# bmsMaster_isospi.net
KiCad netlist of a schematic drawn in Altium Designer
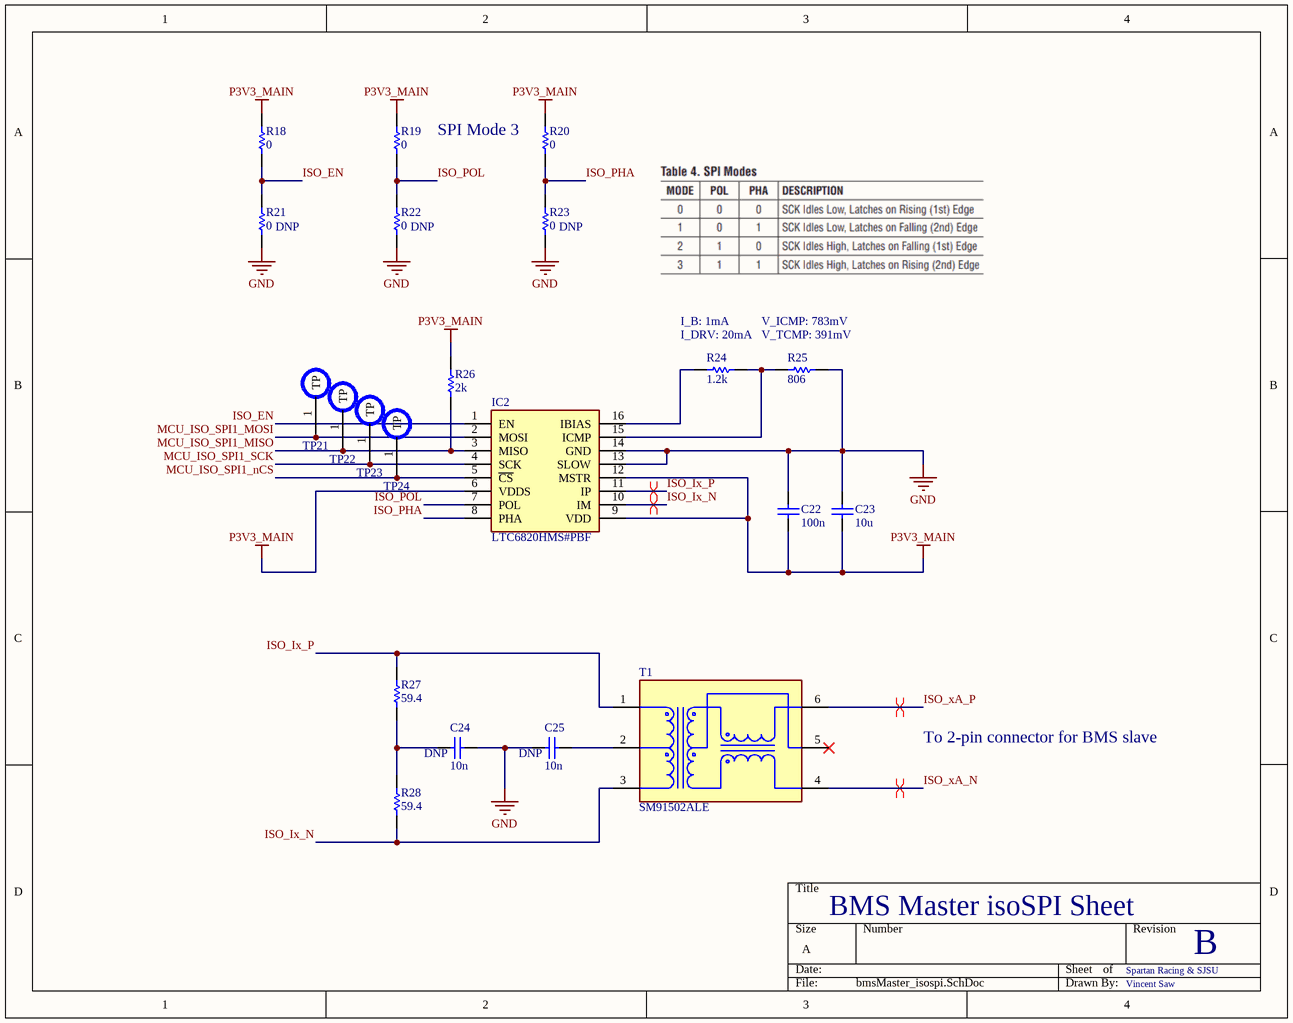
[diagram p0: bmsMaster_isospi.SchDoc]

(export (version "E")
  (design (tool "Eeschema 10.0.6"))
  (components
    (comp (ref "C22")
      (value "100n")
      (footprint "CAPC1608X90N")
      (description "Capacitor")
      (libsource (lib "Simulation Generic Components") (part "Capacitor"))
    )
    (comp (ref "C23")
      (value "10u")
      (footprint "CAPC1608X90N")
      (description "Capacitor")
      (libsource (lib "Simulation Generic Components") (part "Capacitor"))
    )
    (comp (ref "C24")
      (value "10n")
      (footprint "CAPC1608X90N")
      (description "Capacitor")
      (libsource (lib "Simulation Generic Components") (part "Capacitor"))
    )
    (comp (ref "C25")
      (value "10n")
      (footprint "CAPC1608X90N")
      (description "Capacitor")
      (libsource (lib "Simulation Generic Components") (part "Capacitor"))
    )
    (comp (ref "IC2")
      (value "LTC6820HMS#PBF")
      (footprint "SamacSys:SOP50P490X110-16N")
      (description "Integrated Circuit")
      (fields (field (name "MOUSER PART NUMBER") "584-LTC6820HMS#PBF"))
      (libsource (lib "*") (part "LTC6820HMS#PBF"))
    )
    (comp (ref "R18")
      (value "0")
      (footprint "RESC1608X50N")
      (description "Resistor")
      (libsource (lib "Simulation Generic Components") (part "Resistor"))
    )
    (comp (ref "R19")
      (value "0")
      (footprint "RESC1608X50N")
      (description "Resistor")
      (libsource (lib "Simulation Generic Components") (part "Resistor"))
    )
    (comp (ref "R20")
      (value "0")
      (footprint "RESC1608X50N")
      (description "Resistor")
      (libsource (lib "Simulation Generic Components") (part "Resistor"))
    )
    (comp (ref "R21")
      (value "0")
      (footprint "RESC1608X50N")
      (description "Resistor")
      (libsource (lib "Simulation Generic Components") (part "Resistor"))
    )
    (comp (ref "R22")
      (value "0")
      (footprint "RESC1608X50N")
      (description "Resistor")
      (libsource (lib "Simulation Generic Components") (part "Resistor"))
    )
    (comp (ref "R23")
      (value "0")
      (footprint "RESC1608X50N")
      (description "Resistor")
      (libsource (lib "Simulation Generic Components") (part "Resistor"))
    )
    (comp (ref "R24")
      (value "1.2k")
      (footprint "RESC1608X50N")
      (description "Resistor")
      (libsource (lib "Simulation Generic Components") (part "Resistor"))
    )
    (comp (ref "R25")
      (value "806")
      (footprint "RESC1608X50N")
      (description "Resistor")
      (libsource (lib "Simulation Generic Components") (part "Resistor"))
    )
    (comp (ref "R26")
      (value "2k")
      (footprint "RESC1608X50N")
      (description "Resistor")
      (libsource (lib "Simulation Generic Components") (part "Resistor"))
    )
    (comp (ref "R27")
      (value "59.4")
      (footprint "RESC1608X50N")
      (description "Resistor")
      (libsource (lib "Simulation Generic Components") (part "Resistor"))
    )
    (comp (ref "R28")
      (value "59.4")
      (footprint "RESC1608X50N")
      (description "Resistor")
      (libsource (lib "Simulation Generic Components") (part "Resistor"))
    )
    (comp (ref "T1")
      (value "SM91502ALE")
      (footprint "FP-SM91502ALE-MFG")
      (description "BMS XFORMER 1-CH 1000V AECQ +125")
      (fields
        (field (name "MANUFACTURER") "Bourns")
        (field (name "OCTOPART") "https://octopart.com/sm91502ale-bourns-95732123")
      )
      (libsource (lib "Altium Content Vault") (part "554ff5199021d68917f526d8699f58a"))
    )
    (comp (ref "TP21")
      (value "TSTPT")
      (footprint "Testpoint1")
      (libsource (lib "testpoint1") (part "Testpoint1"))
    )
    (comp (ref "TP22")
      (value "TSTPT")
      (footprint "Testpoint1")
      (libsource (lib "testpoint1") (part "Testpoint1"))
    )
    (comp (ref "TP23")
      (value "TSTPT")
      (footprint "Testpoint1")
      (libsource (lib "testpoint1") (part "Testpoint1"))
    )
    (comp (ref "TP24")
      (value "TSTPT")
      (footprint "Testpoint1")
      (libsource (lib "testpoint1") (part "Testpoint1"))
    )
  )
  (nets
    (net (code "1") (name "/ISO_EN") (class "Default")
      (node (ref "IC2") (pin "1") (pinfunction "EN_1") (pintype "passive"))
      (node (ref "R18") (pin "1") (pinfunction "1_1") (pintype "passive"))
      (node (ref "R21") (pin "2") (pinfunction "2_2") (pintype "passive"))
    )
    (net (code "2") (name "/ISO_Ix_N") (class "Default")
      (node (ref "IC2") (pin "10") (pinfunction "IM_10") (pintype "passive"))
      (node (ref "R28") (pin "1") (pinfunction "1_1") (pintype "passive"))
      (node (ref "T1") (pin "3") (pinfunction "3_3") (pintype "passive"))
    )
    (net (code "3") (name "/ISO_Ix_P") (class "Default")
      (node (ref "IC2") (pin "11") (pinfunction "IP_11") (pintype "passive"))
      (node (ref "R27") (pin "2") (pinfunction "2_2") (pintype "passive"))
      (node (ref "T1") (pin "1") (pinfunction "1_1") (pintype "passive"))
    )
    (net (code "4") (name "/ISO_PHA") (class "Default")
      (node (ref "IC2") (pin "8") (pinfunction "PHA_8") (pintype "passive"))
      (node (ref "R20") (pin "1") (pinfunction "1_1") (pintype "passive"))
      (node (ref "R23") (pin "2") (pinfunction "2_2") (pintype "passive"))
    )
    (net (code "5") (name "/ISO_POL") (class "Default")
      (node (ref "IC2") (pin "7") (pinfunction "POL_7") (pintype "passive"))
      (node (ref "R19") (pin "1") (pinfunction "1_1") (pintype "passive"))
      (node (ref "R22") (pin "2") (pinfunction "2_2") (pintype "passive"))
    )
    (net (code "6") (name "/ISO_xA_N") (class "Default")
      (node (ref "T1") (pin "4") (pinfunction "4_4") (pintype "passive"))
    )
    (net (code "7") (name "/ISO_xA_P") (class "Default")
      (node (ref "T1") (pin "6") (pinfunction "6_6") (pintype "passive"))
    )
    (net (code "8") (name "/MCU_ISO_SPI1_MISO") (class "Default")
      (node (ref "IC2") (pin "3") (pinfunction "MISO_3") (pintype "passive"))
      (node (ref "R26") (pin "1") (pinfunction "1_1") (pintype "passive"))
      (node (ref "TP22") (pin "1") (pinfunction "TP_1") (pintype "passive"))
    )
    (net (code "9") (name "/MCU_ISO_SPI1_MOSI") (class "Default")
      (node (ref "IC2") (pin "2") (pinfunction "MOSI_2") (pintype "passive"))
      (node (ref "TP21") (pin "1") (pinfunction "TP_1") (pintype "passive"))
    )
    (net (code "10") (name "/MCU_ISO_SPI1_SCK") (class "Default")
      (node (ref "IC2") (pin "4") (pinfunction "SCK_4") (pintype "passive"))
      (node (ref "TP23") (pin "1") (pinfunction "TP_1") (pintype "passive"))
    )
    (net (code "11") (name "/MCU_ISO_SPI1_nCS") (class "Default")
      (node (ref "IC2") (pin "5") (pinfunction "~{CS}_5") (pintype "passive"))
      (node (ref "TP24") (pin "1") (pinfunction "TP_1") (pintype "passive"))
    )
    (net (code "12") (name "GND") (class "Default")
      (node (ref "C22") (pin "2") (pinfunction "2_2") (pintype "passive"))
      (node (ref "C23") (pin "2") (pinfunction "2_2") (pintype "passive"))
      (node (ref "C24") (pin "1") (pinfunction "1_1") (pintype "passive"))
      (node (ref "C25") (pin "1") (pinfunction "1_1") (pintype "passive"))
      (node (ref "IC2") (pin "13") (pinfunction "SLOW_13") (pintype "passive"))
      (node (ref "IC2") (pin "14") (pinfunction "GND_14") (pintype "passive"))
      (node (ref "R21") (pin "1") (pinfunction "1_1") (pintype "passive"))
      (node (ref "R22") (pin "1") (pinfunction "1_1") (pintype "passive"))
      (node (ref "R23") (pin "1") (pinfunction "1_1") (pintype "passive"))
      (node (ref "R25") (pin "2") (pinfunction "2_2") (pintype "passive"))
    )
    (net (code "13") (name "Net-(C24-Pad2)") (class "Default")
      (node (ref "C24") (pin "2") (pinfunction "2_2") (pintype "passive"))
      (node (ref "R27") (pin "1") (pinfunction "1_1") (pintype "passive"))
      (node (ref "R28") (pin "2") (pinfunction "2_2") (pintype "passive"))
    )
    (net (code "14") (name "Net-(C25-Pad2)") (class "Default")
      (node (ref "C25") (pin "2") (pinfunction "2_2") (pintype "passive"))
      (node (ref "T1") (pin "2") (pinfunction "2_2") (pintype "passive"))
    )
    (net (code "15") (name "Net-(IC2-IBIAS)") (class "Default")
      (node (ref "IC2") (pin "16") (pinfunction "IBIAS_16") (pintype "passive"))
      (node (ref "R24") (pin "1") (pinfunction "1_1") (pintype "passive"))
    )
    (net (code "16") (name "Net-(IC2-ICMP)") (class "Default")
      (node (ref "IC2") (pin "15") (pinfunction "ICMP_15") (pintype "passive"))
      (node (ref "R24") (pin "2") (pinfunction "2_2") (pintype "passive"))
      (node (ref "R25") (pin "1") (pinfunction "1_1") (pintype "passive"))
    )
    (net (code "17") (name "P3V3_MAIN") (class "Default")
      (node (ref "C22") (pin "1") (pinfunction "1_1") (pintype "passive"))
      (node (ref "C23") (pin "1") (pinfunction "1_1") (pintype "passive"))
      (node (ref "IC2") (pin "12") (pinfunction "MSTR_12") (pintype "passive"))
      (node (ref "IC2") (pin "6") (pinfunction "VDDS_6") (pintype "passive"))
      (node (ref "IC2") (pin "9") (pinfunction "VDD_9") (pintype "passive"))
      (node (ref "R18") (pin "2") (pinfunction "2_2") (pintype "passive"))
      (node (ref "R19") (pin "2") (pinfunction "2_2") (pintype "passive"))
      (node (ref "R20") (pin "2") (pinfunction "2_2") (pintype "passive"))
      (node (ref "R26") (pin "2") (pinfunction "2_2") (pintype "passive"))
    )
    (net (code "18") (name "unconnected-(T1-Pad5)") (class "Default")
      (node (ref "T1") (pin "5") (pinfunction "5_5") (pintype "passive+no_connect"))
    )
  )
)
